# balancer.net
KiCad netlist of a schematic drawn in Altium Designer
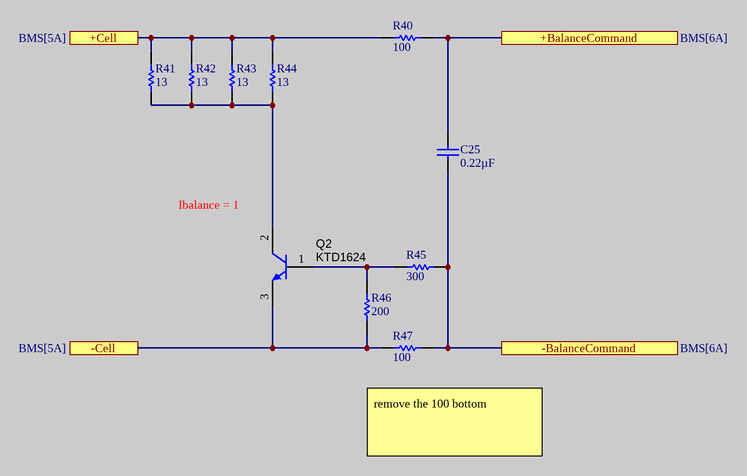
[diagram p0: balancer.SchDoc]

(export (version "E")
  (design (tool "Eeschema 10.0.6"))
  (components
    (comp (ref "C25")
      (value "0.22µF")
      (footprint "CAPC0603")
      (description "Capacitor")
      (fields (field (name "PUBLISHER") "Altium Limited"))
      (libsource (lib "eLIB") (part "Capacitor"))
    )
    (comp (ref "Q2")
      (value "KTD1624")
      (footprint "sot-89")
      (description "BJT 30V 3A 40V 10W SI-NPN")
      (fields
        (field (name "PARTNUMBER") "BSR14")
        (field (name "MANUFACTURER") "Nexperia")
        (field (name "PUBLISHER") "Texas Instruments")
      )
      (libsource (lib "SINA") (part "BSR14, Nexperia"))
    )
    (comp (ref "R40")
      (value "100")
      (footprint "RESC0603")
      (description "0603,0.1W")
      (fields (field (name "PUBLISHER") "Altium Limited"))
      (libsource (lib "eLIB") (part "Resistor"))
    )
    (comp (ref "R41")
      (value "13")
      (footprint "RES2512")
      (description "0603,0.1W")
      (fields (field (name "PUBLISHER") "Altium Limited"))
      (libsource (lib "eLIB") (part "Resistor"))
    )
    (comp (ref "R42")
      (value "13")
      (footprint "RES2512")
      (description "0603,0.1W")
      (fields (field (name "PUBLISHER") "Altium Limited"))
      (libsource (lib "eLIB") (part "Resistor"))
    )
    (comp (ref "R43")
      (value "13")
      (footprint "RES2512")
      (description "0603,0.1W")
      (fields (field (name "PUBLISHER") "Altium Limited"))
      (libsource (lib "eLIB") (part "Resistor"))
    )
    (comp (ref "R44")
      (value "13")
      (footprint "RES2512")
      (description "0603,0.1W")
      (fields (field (name "PUBLISHER") "Altium Limited"))
      (libsource (lib "eLIB") (part "Resistor"))
    )
    (comp (ref "R45")
      (value "300")
      (footprint "RESC0603")
      (description "0603,0.1W")
      (fields (field (name "PUBLISHER") "Altium Limited"))
      (libsource (lib "eLIB") (part "Resistor"))
    )
    (comp (ref "R46")
      (value "200")
      (footprint "RESC0603")
      (description "0603,0.1W")
      (fields (field (name "PUBLISHER") "Altium Limited"))
      (libsource (lib "eLIB") (part "Resistor"))
    )
    (comp (ref "R47")
      (value "100")
      (footprint "RESC0603")
      (description "0603,0.1W")
      (fields (field (name "PUBLISHER") "Altium Limited"))
      (libsource (lib "eLIB") (part "Resistor"))
    )
  )
  (nets
    (net (code "1") (name "/+BalanceCommand") (class "Default")
      (node (ref "C25") (pin "2") (pinfunction "2_2") (pintype "passive"))
      (node (ref "R40") (pin "2") (pinfunction "2_2") (pintype "passive"))
    )
    (net (code "2") (name "/+Cell") (class "Default")
      (node (ref "R40") (pin "1") (pinfunction "1_1") (pintype "passive"))
      (node (ref "R41") (pin "1") (pinfunction "1_1") (pintype "passive"))
      (node (ref "R42") (pin "1") (pinfunction "1_1") (pintype "passive"))
      (node (ref "R43") (pin "1") (pinfunction "1_1") (pintype "passive"))
      (node (ref "R44") (pin "1") (pinfunction "1_1") (pintype "passive"))
    )
    (net (code "3") (name "/-BalanceCommand") (class "Default")
      (node (ref "C25") (pin "1") (pinfunction "1_1") (pintype "passive"))
      (node (ref "R45") (pin "2") (pinfunction "2_2") (pintype "passive"))
      (node (ref "R47") (pin "2") (pinfunction "2_2") (pintype "passive"))
    )
    (net (code "4") (name "/-Cell") (class "Default")
      (node (ref "Q2") (pin "3") (pinfunction "E_3") (pintype "passive"))
      (node (ref "R46") (pin "1") (pinfunction "1_1") (pintype "passive"))
      (node (ref "R47") (pin "1") (pinfunction "1_1") (pintype "passive"))
    )
    (net (code "5") (name "Net-(Q2-B)") (class "Default")
      (node (ref "Q2") (pin "1") (pinfunction "B_1") (pintype "passive"))
      (node (ref "R45") (pin "1") (pinfunction "1_1") (pintype "passive"))
      (node (ref "R46") (pin "2") (pinfunction "2_2") (pintype "passive"))
    )
    (net (code "6") (name "Net-(Q2-C)") (class "Default")
      (node (ref "Q2") (pin "2") (pinfunction "C_2") (pintype "passive"))
      (node (ref "R41") (pin "2") (pinfunction "2_2") (pintype "passive"))
      (node (ref "R42") (pin "2") (pinfunction "2_2") (pintype "passive"))
      (node (ref "R43") (pin "2") (pinfunction "2_2") (pintype "passive"))
      (node (ref "R44") (pin "2") (pinfunction "2_2") (pintype "passive"))
    )
  )
)
